# Sheet1.net
KiCad netlist of a schematic drawn in Altium Designer
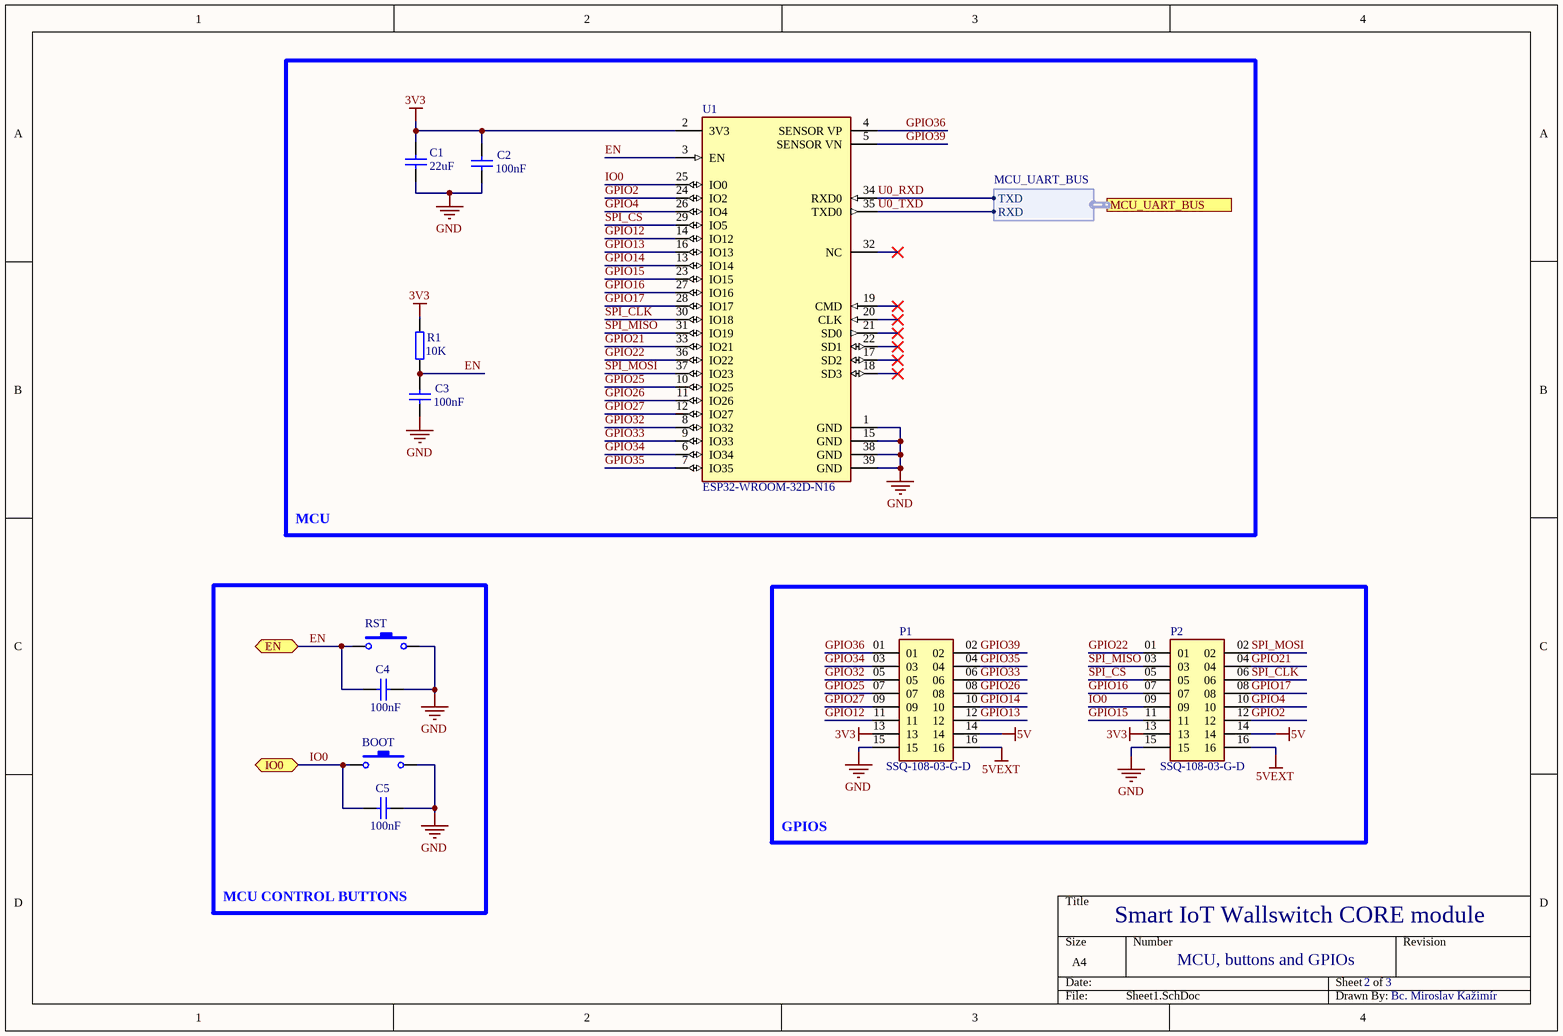
[diagram p0: Sheet1.SchDoc]

(export (version "E")
  (design (tool "Eeschema 10.0.6"))
  (components
    (comp (ref "BOOT")
      (value "SKRKAHE020")
      (footprint "SKRKAEE020")
      (description "Switch Tactile N.O. SPST Round Button Gull Wing 0.05A 12VDC 0.98N SMD T/R")
      (fields (field (name "MANUFACTURER") "Alps Electric"))
      (libsource (lib "Schlib1") (part "SKRKAHE020"))
    )
    (comp (ref "C1")
      (value "GRM21BR61A226ME51L")
      (footprint "FP-GRM21B-0_15-IPC_A")
      (description "贴片电容（MLCC） 22µF ±20% 10V X5R 0805")
      (fields
        (field (name "MANUFACTURER") "Murata")
        (field (name "CAPACITANCE") "22uF")
        (field (name "TOLERANCE") "20%")
      )
      (libsource (lib "Schlib1") (part "GRM21BR61A226ME51L"))
    )
    (comp (ref "C2")
      (value "C0805C104K5RAC7411")
      (footprint "FP-C0805C-DN-IPC_A")
      (description "Cap Ceramic 0.1uF 50V X7R 10% SMD 0805 125°C Paper T/R")
      (fields
        (field (name "MANUFACTURER") "KEMET")
        (field (name "TOLERANCE") "10%")
        (field (name "CAPACITANCE") "100nF")
      )
      (libsource (lib "Schlib1") (part "C0805C104K5RAC7411"))
    )
    (comp (ref "C3")
      (value "C0805C104K5RAC7411")
      (footprint "FP-C0805C-DN-IPC_A")
      (description "Cap Ceramic 0.1uF 50V X7R 10% SMD 0805 125°C Paper T/R")
      (fields
        (field (name "MANUFACTURER") "KEMET")
        (field (name "TOLERANCE") "10%")
        (field (name "CAPACITANCE") "100nF")
      )
      (libsource (lib "Schlib1") (part "C0805C104K5RAC7411"))
    )
    (comp (ref "C4")
      (value "C0805C104K5RAC7411")
      (footprint "FP-C0805C-DN-IPC_A")
      (description "Cap Ceramic 0.1uF 50V X7R 10% SMD 0805 125°C Paper T/R")
      (fields
        (field (name "MANUFACTURER") "KEMET")
        (field (name "TOLERANCE") "10%")
        (field (name "CAPACITANCE") "100nF")
      )
      (libsource (lib "Schlib1") (part "C0805C104K5RAC7411"))
    )
    (comp (ref "C5")
      (value "C0805C104K5RAC7411")
      (footprint "FP-C0805C-DN-IPC_A")
      (description "Cap Ceramic 0.1uF 50V X7R 10% SMD 0805 125°C Paper T/R")
      (fields
        (field (name "MANUFACTURER") "KEMET")
        (field (name "TOLERANCE") "10%")
        (field (name "CAPACITANCE") "100nF")
      )
      (libsource (lib "Schlib1") (part "C0805C104K5RAC7411"))
    )
    (comp (ref "P1")
      (value "SSQ-108-03-G-D")
      (footprint "SAMTEC_SSQ-108-XX-X-D")
      (description "Headers & Wire Housings Tiger Buy Socket Strip with Square Tails, 0.100 Pitch")
      (fields (field (name "MANUFACTURER") "Samtec"))
      (libsource (lib "Schlib1") (part "SSQ-108-03-G-D"))
    )
    (comp (ref "P2")
      (value "SSQ-108-03-G-D")
      (footprint "SAMTEC_SSQ-108-XX-X-D")
      (description "Headers & Wire Housings Tiger Buy Socket Strip with Square Tails, 0.100 Pitch")
      (fields (field (name "MANUFACTURER") "Samtec"))
      (libsource (lib "Schlib1") (part "SSQ-108-03-G-D"))
    )
    (comp (ref "R1")
      (value "ERJ-UP6J103V")
      (footprint "RESC2012X70N")
      (description "Res 10K Ohm 5% 1/2W 0805")
      (fields (field (name "MANUFACTURER") "Panasonic") (field (name "RESISTANCE") "10K"))
      (libsource (lib "Schlib1") (part "ERJ-UP6J103V"))
    )
    (comp (ref "RST")
      (value "SKRKAHE020")
      (footprint "SKRKAEE020")
      (description "Switch Tactile N.O. SPST Round Button Gull Wing 0.05A 12VDC 0.98N SMD T/R")
      (fields (field (name "MANUFACTURER") "Alps Electric"))
      (libsource (lib "Schlib1") (part "SKRKAHE020"))
    )
    (comp (ref "U1")
      (value "ESP32-WROOM-32D-N16")
      (footprint "FP-ESP32-WROOM-32D_16MB-MFG")
      (description "Bluetooth and Wi-Fi Module\r\n2.4GHz to 2.5GHz 2.7V to 3.6V 16MB Flash\r\n38-Pin SMD Module")
      (fields (field (name "MANUFACTURER") "Espressif Systems"))
      (libsource (lib "Schlib1") (part "ESP32-WROOM-32D-N16"))
    )
  )
  (nets
    (net (code "2") (name "/EN") (class "Default")
      (node (ref "C3") (pin "1") (pinfunction "1_1") (pintype "passive"))
      (node (ref "C4") (pin "1") (pinfunction "1_1") (pintype "passive"))
      (node (ref "R1") (pin "2") (pinfunction "2_2") (pintype "passive"))
      (node (ref "RST") (pin "1") (pinfunction "1_1") (pintype "passive"))
      (node (ref "U1") (pin "3") (pinfunction "EN_3") (pintype "input"))
    )
    (net (code "3") (name "/GPIO2") (class "Default")
      (node (ref "P2") (pin "12") (pinfunction "12_12") (pintype "passive"))
      (node (ref "U1") (pin "24") (pinfunction "IO2_24") (pintype "bidirectional"))
    )
    (net (code "4") (name "/GPIO4") (class "Default")
      (node (ref "P2") (pin "10") (pinfunction "10_10") (pintype "passive"))
      (node (ref "U1") (pin "26") (pinfunction "IO4_26") (pintype "bidirectional"))
    )
    (net (code "5") (name "/GPIO12") (class "Default")
      (node (ref "P1") (pin "11") (pinfunction "11_11") (pintype "passive"))
      (node (ref "U1") (pin "14") (pinfunction "IO12_14") (pintype "bidirectional"))
    )
    (net (code "6") (name "/GPIO13") (class "Default")
      (node (ref "P1") (pin "12") (pinfunction "12_12") (pintype "passive"))
      (node (ref "U1") (pin "16") (pinfunction "IO13_16") (pintype "bidirectional"))
    )
    (net (code "7") (name "/GPIO14") (class "Default")
      (node (ref "P1") (pin "10") (pinfunction "10_10") (pintype "passive"))
      (node (ref "U1") (pin "13") (pinfunction "IO14_13") (pintype "bidirectional"))
    )
    (net (code "8") (name "/GPIO15") (class "Default")
      (node (ref "P2") (pin "11") (pinfunction "11_11") (pintype "passive"))
      (node (ref "U1") (pin "23") (pinfunction "IO15_23") (pintype "bidirectional"))
    )
    (net (code "9") (name "/GPIO16") (class "Default")
      (node (ref "P2") (pin "07") (pinfunction "07_07") (pintype "passive"))
      (node (ref "U1") (pin "27") (pinfunction "IO16_27") (pintype "bidirectional"))
    )
    (net (code "10") (name "/GPIO17") (class "Default")
      (node (ref "P2") (pin "08") (pinfunction "08_08") (pintype "passive"))
      (node (ref "U1") (pin "28") (pinfunction "IO17_28") (pintype "bidirectional"))
    )
    (net (code "11") (name "/GPIO21") (class "Default")
      (node (ref "P2") (pin "04") (pinfunction "04_04") (pintype "passive"))
      (node (ref "U1") (pin "33") (pinfunction "IO21_33") (pintype "bidirectional"))
    )
    (net (code "12") (name "/GPIO22") (class "Default")
      (node (ref "P2") (pin "01") (pinfunction "01_01") (pintype "passive"))
      (node (ref "U1") (pin "36") (pinfunction "IO22_36") (pintype "bidirectional"))
    )
    (net (code "13") (name "/GPIO25") (class "Default")
      (node (ref "P1") (pin "07") (pinfunction "07_07") (pintype "passive"))
      (node (ref "U1") (pin "10") (pinfunction "IO25_10") (pintype "bidirectional"))
    )
    (net (code "14") (name "/GPIO26") (class "Default")
      (node (ref "P1") (pin "08") (pinfunction "08_08") (pintype "passive"))
      (node (ref "U1") (pin "11") (pinfunction "IO26_11") (pintype "bidirectional"))
    )
    (net (code "15") (name "/GPIO27") (class "Default")
      (node (ref "P1") (pin "09") (pinfunction "09_09") (pintype "passive"))
      (node (ref "U1") (pin "12") (pinfunction "IO27_12") (pintype "bidirectional"))
    )
    (net (code "16") (name "/GPIO32") (class "Default")
      (node (ref "P1") (pin "05") (pinfunction "05_05") (pintype "passive"))
      (node (ref "U1") (pin "8") (pinfunction "IO32_8") (pintype "bidirectional"))
    )
    (net (code "17") (name "/GPIO33") (class "Default")
      (node (ref "P1") (pin "06") (pinfunction "06_06") (pintype "passive"))
      (node (ref "U1") (pin "9") (pinfunction "IO33_9") (pintype "bidirectional"))
    )
    (net (code "18") (name "/GPIO34") (class "Default")
      (node (ref "P1") (pin "03") (pinfunction "03_03") (pintype "passive"))
      (node (ref "U1") (pin "6") (pinfunction "IO34_6") (pintype "bidirectional"))
    )
    (net (code "19") (name "/GPIO35") (class "Default")
      (node (ref "P1") (pin "04") (pinfunction "04_04") (pintype "passive"))
      (node (ref "U1") (pin "7") (pinfunction "IO35_7") (pintype "bidirectional"))
    )
    (net (code "20") (name "/GPIO36") (class "Default")
      (node (ref "P1") (pin "01") (pinfunction "01_01") (pintype "passive"))
      (node (ref "U1") (pin "4") (pinfunction "SENSOR_VP_4") (pintype "passive"))
    )
    (net (code "21") (name "/GPIO39") (class "Default")
      (node (ref "P1") (pin "02") (pinfunction "02_02") (pintype "passive"))
      (node (ref "U1") (pin "5") (pinfunction "SENSOR_VN_5") (pintype "passive"))
    )
    (net (code "22") (name "/IO0") (class "Default")
      (node (ref "BOOT") (pin "1") (pinfunction "1_1") (pintype "passive"))
      (node (ref "C5") (pin "1") (pinfunction "1_1") (pintype "passive"))
      (node (ref "P2") (pin "09") (pinfunction "09_09") (pintype "passive"))
      (node (ref "U1") (pin "25") (pinfunction "IO0_25") (pintype "bidirectional"))
    )
    (net (code "23") (name "/SPI_CLK") (class "Default")
      (node (ref "P2") (pin "06") (pinfunction "06_06") (pintype "passive"))
      (node (ref "U1") (pin "30") (pinfunction "IO18_30") (pintype "bidirectional"))
    )
    (net (code "24") (name "/SPI_CS") (class "Default")
      (node (ref "P2") (pin "05") (pinfunction "05_05") (pintype "passive"))
      (node (ref "U1") (pin "29") (pinfunction "IO5_29") (pintype "bidirectional"))
    )
    (net (code "25") (name "/SPI_MISO") (class "Default")
      (node (ref "P2") (pin "03") (pinfunction "03_03") (pintype "passive"))
      (node (ref "U1") (pin "31") (pinfunction "IO19_31") (pintype "bidirectional"))
    )
    (net (code "26") (name "/SPI_MOSI") (class "Default")
      (node (ref "P2") (pin "02") (pinfunction "02_02") (pintype "passive"))
      (node (ref "U1") (pin "37") (pinfunction "IO23_37") (pintype "bidirectional"))
    )
    (net (code "27") (name "/U0_RXD") (class "Default")
      (node (ref "U1") (pin "34") (pinfunction "RXD0_34") (pintype "input"))
    )
    (net (code "28") (name "/U0_TXD") (class "Default")
      (node (ref "U1") (pin "35") (pinfunction "TXD0_35") (pintype "output"))
    )
    (net (code "30") (name "3V3") (class "Default")
      (node (ref "C1") (pin "1") (pinfunction "1_1") (pintype "passive"))
      (node (ref "C2") (pin "1") (pinfunction "1_1") (pintype "passive"))
      (node (ref "P1") (pin "13") (pinfunction "13_13") (pintype "passive"))
      (node (ref "P2") (pin "13") (pinfunction "13_13") (pintype "passive"))
      (node (ref "R1") (pin "1") (pinfunction "1_1") (pintype "passive"))
      (node (ref "U1") (pin "2") (pinfunction "3V3_2") (pintype "power_in"))
    )
    (net (code "31") (name "5V") (class "Default")
      (node (ref "P1") (pin "14") (pinfunction "14_14") (pintype "passive"))
      (node (ref "P2") (pin "14") (pinfunction "14_14") (pintype "passive"))
    )
    (net (code "32") (name "5VEXT") (class "Default")
      (node (ref "P1") (pin "16") (pinfunction "16_16") (pintype "passive"))
      (node (ref "P2") (pin "16") (pinfunction "16_16") (pintype "passive"))
    )
    (net (code "33") (name "GND") (class "Default")
      (node (ref "BOOT") (pin "2") (pinfunction "2_2") (pintype "passive"))
      (node (ref "C1") (pin "2") (pinfunction "2_2") (pintype "passive"))
      (node (ref "C2") (pin "2") (pinfunction "2_2") (pintype "passive"))
      (node (ref "C3") (pin "2") (pinfunction "2_2") (pintype "passive"))
      (node (ref "C4") (pin "2") (pinfunction "2_2") (pintype "passive"))
      (node (ref "C5") (pin "2") (pinfunction "2_2") (pintype "passive"))
      (node (ref "P1") (pin "15") (pinfunction "15_15") (pintype "passive"))
      (node (ref "P2") (pin "15") (pinfunction "15_15") (pintype "passive"))
      (node (ref "RST") (pin "2") (pinfunction "2_2") (pintype "passive"))
      (node (ref "U1") (pin "1") (pinfunction "GND_1") (pintype "power_in"))
      (node (ref "U1") (pin "15") (pinfunction "GND_15") (pintype "power_in"))
      (node (ref "U1") (pin "38") (pinfunction "GND_38") (pintype "power_in"))
      (node (ref "U1") (pin "39") (pinfunction "GND_39") (pintype "power_in"))
    )
    (net (code "34") (name "unconnected-(U1-CLK-Pad20)") (class "Default")
      (node (ref "U1") (pin "20") (pinfunction "CLK_20") (pintype "input+no_connect"))
    )
    (net (code "35") (name "unconnected-(U1-CMD-Pad19)") (class "Default")
      (node (ref "U1") (pin "19") (pinfunction "CMD_19") (pintype "input+no_connect"))
    )
    (net (code "36") (name "unconnected-(U1-NC-Pad32)") (class "Default")
      (node (ref "U1") (pin "32") (pinfunction "NC_32") (pintype "passive+no_connect"))
    )
    (net (code "37") (name "unconnected-(U1-SD0-Pad21)") (class "Default")
      (node (ref "U1") (pin "21") (pinfunction "SD0_21") (pintype "output+no_connect"))
    )
    (net (code "38") (name "unconnected-(U1-SD1-Pad22)") (class "Default")
      (node (ref "U1") (pin "22") (pinfunction "SD1_22") (pintype "bidirectional+no_connect"))
    )
    (net (code "39") (name "unconnected-(U1-SD2-Pad17)") (class "Default")
      (node (ref "U1") (pin "17") (pinfunction "SD2_17") (pintype "bidirectional+no_connect"))
    )
    (net (code "40") (name "unconnected-(U1-SD3-Pad18)") (class "Default")
      (node (ref "U1") (pin "18") (pinfunction "SD3_18") (pintype "bidirectional+no_connect"))
    )
  )
)
